# A7_CONNECTOR_V2_0.net
KiCad netlist of a schematic drawn in Altium Designer
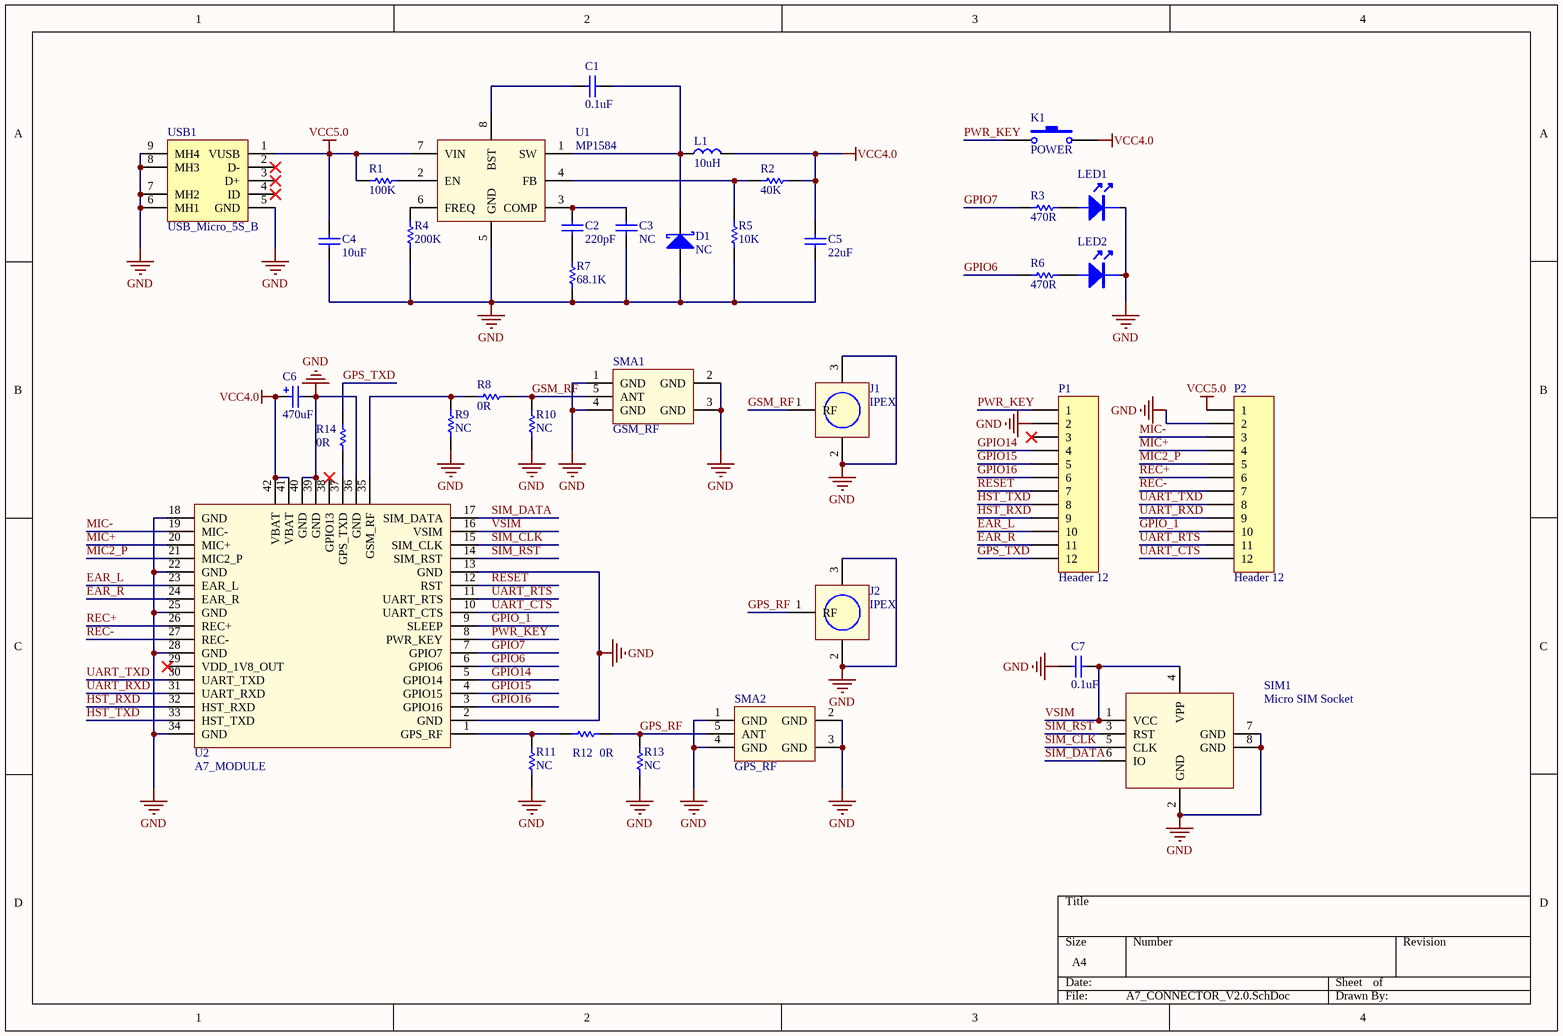
[diagram p0: A7_CONNECTOR_V2.0.SchDoc]

(export (version "E")
  (design (tool "Eeschema 10.0.6"))
  (components
    (comp (ref "C1") (value "0.1uF") (footprint "C0402") (libsource (lib "Schlib1") (part "Cap")))
    (comp (ref "C2") (value "220pF") (footprint "C0402") (libsource (lib "Schlib1") (part "Cap")))
    (comp (ref "C3") (value "NC") (footprint "C0402") (libsource (lib "Schlib1") (part "Cap")))
    (comp (ref "C4") (value "10uF") (footprint "C0603") (libsource (lib "Schlib1") (part "Cap")))
    (comp (ref "C5") (value "22uF") (footprint "C0805") (libsource (lib "Schlib1") (part "Cap")))
    (comp (ref "C6") (value "470uF") (footprint "D7343-31") (libsource (lib "Schlib1") (part "Cap+")))
    (comp (ref "C7") (value "0.1uF") (footprint "C0402") (libsource (lib "Schlib1") (part "Cap")))
    (comp (ref "D1")
      (value "NC")
      (footprint "SOD-123")
      (description "Schottky Diode")
      (fields (field (name "PUBLISHER") "Altium Limited"))
      (libsource (lib "Schlib1") (part "D Schottky"))
    )
    (comp (ref "J1") (value "IPEX") (footprint "IPEX") (libsource (lib "Schlib1") (part "IPEX")))
    (comp (ref "J2") (value "IPEX") (footprint "IPEX") (libsource (lib "Schlib1") (part "IPEX")))
    (comp (ref "K1")
      (value "POWER")
      (footprint "KEY-6*6-SMD")
      (fields (field (name "PUBLISHER") "Altium Limited"))
      (libsource (lib "Schlib1") (part "KEY"))
    )
    (comp (ref "L1") (value "10uH") (footprint "L0805") (libsource (lib "Schlib1") (part "L")))
    (comp (ref "LED1")
      (value "~")
      (footprint "LED_0603")
      (description "SMD0603 LED")
      (libsource (lib "Schlib1") (part "LED"))
    )
    (comp (ref "LED2")
      (value "~")
      (footprint "LED_0603")
      (description "SMD0603 LED")
      (libsource (lib "Schlib1") (part "LED"))
    )
    (comp (ref "P1")
      (value "Header 12")
      (footprint "HDR1X12")
      (description "Header, 12-Pin")
      (fields (field (name "PUBLISHER") "Altium Limited"))
      (libsource (lib "Miscellaneous Connectors") (part "Header 12"))
    )
    (comp (ref "P2")
      (value "Header 12")
      (footprint "HDR1X12")
      (description "Header, 12-Pin")
      (fields (field (name "PUBLISHER") "Altium Limited"))
      (libsource (lib "Miscellaneous Connectors") (part "Header 12"))
    )
    (comp (ref "R1") (value "100K") (footprint "R0402") (libsource (lib "Schlib1") (part "Res")))
    (comp (ref "R2") (value "40K") (footprint "R0402") (libsource (lib "Schlib1") (part "Res")))
    (comp (ref "R3") (value "470R") (footprint "R0402") (libsource (lib "Schlib1") (part "Res")))
    (comp (ref "R4") (value "200K") (footprint "R0402") (libsource (lib "Schlib1") (part "Res")))
    (comp (ref "R5") (value "10K") (footprint "R0402") (libsource (lib "Schlib1") (part "Res")))
    (comp (ref "R6") (value "470R") (footprint "R0402") (libsource (lib "Schlib1") (part "Res")))
    (comp (ref "R7") (value "68.1K") (footprint "R0402") (libsource (lib "Schlib1") (part "Res")))
    (comp (ref "R8") (value "0R") (footprint "R0402") (libsource (lib "Schlib1") (part "Res")))
    (comp (ref "R9") (value "NC") (footprint "R0402") (libsource (lib "Schlib1") (part "Res")))
    (comp (ref "R10") (value "NC") (footprint "R0402") (libsource (lib "Schlib1") (part "Res")))
    (comp (ref "R11") (value "NC") (footprint "R0402") (libsource (lib "Schlib1") (part "Res")))
    (comp (ref "R12") (value "0R") (footprint "R0402") (libsource (lib "Schlib1") (part "Res")))
    (comp (ref "R13") (value "NC") (footprint "R0402") (libsource (lib "Schlib1") (part "Res")))
    (comp (ref "R14") (value "0R") (footprint "R0402") (libsource (lib "Schlib1") (part "Res")))
    (comp (ref "SIM1")
      (value "Micro SIM Socket")
      (footprint "SIM")
      (libsource (lib "Schlib1") (part "Micro SIM"))
    )
    (comp (ref "SMA1") (value "GSM_RF") (footprint "SMA") (libsource (lib "Schlib1") (part "SMA")))
    (comp (ref "SMA2") (value "GPS_RF") (footprint "SMA") (libsource (lib "Schlib1") (part "SMA")))
    (comp (ref "U1") (value "MP1584") (footprint "SOIC8E") (libsource (lib "Schlib1") (part "MP1584")))
    (comp (ref "U2")
      (value "A7_MODULE")
      (footprint "A6_GPS_MODULE")
      (libsource (lib "Schlib1") (part "A6_GPS_MODULE"))
    )
    (comp (ref "USB1")
      (value "USB_Micro_5S_B")
      (footprint "USB_MICRO_5S_B")
      (description "USB micro female SMT with 4 fixed foot")
      (libsource (lib "Schlib1") (part "USB_Micro_5S_B"))
    )
  )
  (nets
    (net (code "1") (name "/EAR_L") (class "Default")
      (node (ref "P1") (pin "10") (pinfunction "10_10") (pintype "passive"))
      (node (ref "U2") (pin "23") (pinfunction "EAR_L_23") (pintype "passive"))
    )
    (net (code "2") (name "/EAR_R") (class "Default")
      (node (ref "P1") (pin "11") (pinfunction "11_11") (pintype "passive"))
      (node (ref "U2") (pin "24") (pinfunction "EAR_R_24") (pintype "passive"))
    )
    (net (code "3") (name "/GPIO6") (class "Default")
      (node (ref "R6") (pin "1") (pinfunction "1_1") (pintype "passive"))
      (node (ref "U2") (pin "6") (pinfunction "GPIO6_6") (pintype "passive"))
    )
    (net (code "4") (name "/GPIO7") (class "Default")
      (node (ref "R3") (pin "1") (pinfunction "1_1") (pintype "passive"))
      (node (ref "U2") (pin "7") (pinfunction "GPIO7_7") (pintype "passive"))
    )
    (net (code "5") (name "/GPIO14") (class "Default")
      (node (ref "P1") (pin "4") (pinfunction "4_4") (pintype "passive"))
      (node (ref "U2") (pin "5") (pinfunction "GPIO14_5") (pintype "passive"))
    )
    (net (code "6") (name "/GPIO15") (class "Default")
      (node (ref "P1") (pin "5") (pinfunction "5_5") (pintype "passive"))
      (node (ref "U2") (pin "4") (pinfunction "GPIO15_4") (pintype "passive"))
    )
    (net (code "7") (name "/GPIO16") (class "Default")
      (node (ref "P1") (pin "6") (pinfunction "6_6") (pintype "passive"))
      (node (ref "U2") (pin "3") (pinfunction "GPIO16_3") (pintype "passive"))
    )
    (net (code "8") (name "/GPIO_1") (class "Default")
      (node (ref "P2") (pin "10") (pinfunction "10_10") (pintype "passive"))
      (node (ref "U2") (pin "9") (pinfunction "SLEEP_9") (pintype "passive"))
    )
    (net (code "9") (name "/GPS_RF") (class "Default")
      (node (ref "J2") (pin "1") (pinfunction "RF_1") (pintype "passive"))
      (node (ref "R12") (pin "2") (pinfunction "2_2") (pintype "passive"))
      (node (ref "R13") (pin "2") (pinfunction "2_2") (pintype "passive"))
      (node (ref "SMA2") (pin "5") (pinfunction "ANT_5") (pintype "passive"))
    )
    (net (code "10") (name "/GPS_TXD") (class "Default")
      (node (ref "P1") (pin "12") (pinfunction "12_12") (pintype "passive"))
      (node (ref "R14") (pin "2") (pinfunction "2_2") (pintype "passive"))
    )
    (net (code "11") (name "/GSM_RF") (class "Default")
      (node (ref "J1") (pin "1") (pinfunction "RF_1") (pintype "passive"))
      (node (ref "R10") (pin "2") (pinfunction "2_2") (pintype "passive"))
      (node (ref "R8") (pin "2") (pinfunction "2_2") (pintype "passive"))
      (node (ref "SMA1") (pin "5") (pinfunction "ANT_5") (pintype "passive"))
    )
    (net (code "12") (name "/HST_RXD") (class "Default")
      (node (ref "P1") (pin "9") (pinfunction "9_9") (pintype "passive"))
      (node (ref "U2") (pin "32") (pinfunction "HST_RXD_32") (pintype "passive"))
    )
    (net (code "13") (name "/HST_TXD") (class "Default")
      (node (ref "P1") (pin "8") (pinfunction "8_8") (pintype "passive"))
      (node (ref "U2") (pin "33") (pinfunction "HST_TXD_33") (pintype "passive"))
    )
    (net (code "14") (name "/MIC+") (class "Default")
      (node (ref "P2") (pin "4") (pinfunction "4_4") (pintype "passive"))
      (node (ref "U2") (pin "20") (pinfunction "MIC+_20") (pintype "passive"))
    )
    (net (code "15") (name "/MIC-") (class "Default")
      (node (ref "P2") (pin "3") (pinfunction "3_3") (pintype "passive"))
      (node (ref "U2") (pin "19") (pinfunction "MIC-_19") (pintype "passive"))
    )
    (net (code "16") (name "/MIC2_P") (class "Default")
      (node (ref "P2") (pin "5") (pinfunction "5_5") (pintype "passive"))
      (node (ref "U2") (pin "21") (pinfunction "MIC2_P_21") (pintype "passive"))
    )
    (net (code "17") (name "/PWR_KEY") (class "Default")
      (node (ref "K1") (pin "1") (pinfunction "1_1") (pintype "passive"))
      (node (ref "P1") (pin "1") (pinfunction "1_1") (pintype "passive"))
      (node (ref "U2") (pin "8") (pinfunction "PWR_KEY_8") (pintype "passive"))
    )
    (net (code "18") (name "/REC+") (class "Default")
      (node (ref "P2") (pin "6") (pinfunction "6_6") (pintype "passive"))
      (node (ref "U2") (pin "26") (pinfunction "REC+_26") (pintype "passive"))
    )
    (net (code "19") (name "/REC-") (class "Default")
      (node (ref "P2") (pin "7") (pinfunction "7_7") (pintype "passive"))
      (node (ref "U2") (pin "27") (pinfunction "REC-_27") (pintype "passive"))
    )
    (net (code "20") (name "/RESET") (class "Default")
      (node (ref "P1") (pin "7") (pinfunction "7_7") (pintype "passive"))
      (node (ref "U2") (pin "12") (pinfunction "RST_12") (pintype "passive"))
    )
    (net (code "21") (name "/SIM_CLK") (class "Default")
      (node (ref "SIM1") (pin "5") (pinfunction "CLK_5") (pintype "passive"))
      (node (ref "U2") (pin "15") (pinfunction "SIM_CLK_15") (pintype "passive"))
    )
    (net (code "22") (name "/SIM_DATA") (class "Default")
      (node (ref "SIM1") (pin "6") (pinfunction "IO_6") (pintype "passive"))
      (node (ref "U2") (pin "17") (pinfunction "SIM_DATA_17") (pintype "passive"))
    )
    (net (code "23") (name "/SIM_RST") (class "Default")
      (node (ref "SIM1") (pin "3") (pinfunction "RST_3") (pintype "passive"))
      (node (ref "U2") (pin "14") (pinfunction "SIM_RST_14") (pintype "passive"))
    )
    (net (code "24") (name "/UART_CTS") (class "Default")
      (node (ref "P2") (pin "12") (pinfunction "12_12") (pintype "passive"))
      (node (ref "U2") (pin "10") (pinfunction "UART_CTS_10") (pintype "passive"))
    )
    (net (code "25") (name "/UART_RTS") (class "Default")
      (node (ref "P2") (pin "11") (pinfunction "11_11") (pintype "passive"))
      (node (ref "U2") (pin "11") (pinfunction "UART_RTS_11") (pintype "passive"))
    )
    (net (code "26") (name "/UART_RXD") (class "Default")
      (node (ref "P2") (pin "9") (pinfunction "9_9") (pintype "passive"))
      (node (ref "U2") (pin "31") (pinfunction "UART_RXD_31") (pintype "passive"))
    )
    (net (code "27") (name "/UART_TXD") (class "Default")
      (node (ref "P2") (pin "8") (pinfunction "8_8") (pintype "passive"))
      (node (ref "U2") (pin "30") (pinfunction "UART_TXD_30") (pintype "passive"))
    )
    (net (code "28") (name "/VSIM") (class "Default")
      (node (ref "C7") (pin "1") (pinfunction "1_1") (pintype "passive"))
      (node (ref "SIM1") (pin "1") (pinfunction "VCC_1") (pintype "passive"))
      (node (ref "SIM1") (pin "4") (pinfunction "VPP_4") (pintype "passive"))
      (node (ref "U2") (pin "16") (pinfunction "VSIM_16") (pintype "passive"))
    )
    (net (code "29") (name "GND") (class "Default")
      (node (ref "C3") (pin "1") (pinfunction "1_1") (pintype "passive"))
      (node (ref "C4") (pin "1") (pinfunction "1_1") (pintype "passive"))
      (node (ref "C5") (pin "1") (pinfunction "1_1") (pintype "passive"))
      (node (ref "C6") (pin "2") (pinfunction "2_2") (pintype "passive"))
      (node (ref "C7") (pin "2") (pinfunction "2_2") (pintype "passive"))
      (node (ref "D1") (pin "1") (pinfunction "A_1") (pintype "passive"))
      (node (ref "J1") (pin "2") (pinfunction "GND_2") (pintype "passive"))
      (node (ref "J1") (pin "3") (pinfunction "GND_3") (pintype "passive"))
      (node (ref "J2") (pin "2") (pinfunction "GND_2") (pintype "passive"))
      (node (ref "J2") (pin "3") (pinfunction "GND_3") (pintype "passive"))
      (node (ref "LED1") (pin "2") (pinfunction "K_2") (pintype "passive"))
      (node (ref "LED2") (pin "2") (pinfunction "K_2") (pintype "passive"))
      (node (ref "P1") (pin "2") (pinfunction "2_2") (pintype "passive"))
      (node (ref "P2") (pin "2") (pinfunction "2_2") (pintype "passive"))
      (node (ref "R10") (pin "1") (pinfunction "1_1") (pintype "passive"))
      (node (ref "R11") (pin "1") (pinfunction "1_1") (pintype "passive"))
      (node (ref "R13") (pin "1") (pinfunction "1_1") (pintype "passive"))
      (node (ref "R4") (pin "1") (pinfunction "1_1") (pintype "passive"))
      (node (ref "R5") (pin "1") (pinfunction "1_1") (pintype "passive"))
      (node (ref "R7") (pin "1") (pinfunction "1_1") (pintype "passive"))
      (node (ref "R9") (pin "1") (pinfunction "1_1") (pintype "passive"))
      (node (ref "SIM1") (pin "2") (pinfunction "GND_2") (pintype "passive"))
      (node (ref "SIM1") (pin "7") (pinfunction "GND_7") (pintype "passive"))
      (node (ref "SIM1") (pin "8") (pinfunction "GND_8") (pintype "passive"))
      (node (ref "SMA1") (pin "1") (pinfunction "GND_1") (pintype "passive"))
      (node (ref "SMA1") (pin "2") (pinfunction "GND_2") (pintype "passive"))
      (node (ref "SMA1") (pin "3") (pinfunction "GND_3") (pintype "passive"))
      (node (ref "SMA1") (pin "4") (pinfunction "GND_4") (pintype "passive"))
      (node (ref "SMA2") (pin "1") (pinfunction "GND_1") (pintype "passive"))
      (node (ref "SMA2") (pin "2") (pinfunction "GND_2") (pintype "passive"))
      (node (ref "SMA2") (pin "3") (pinfunction "GND_3") (pintype "passive"))
      (node (ref "SMA2") (pin "4") (pinfunction "GND_4") (pintype "passive"))
      (node (ref "U1") (pin "5") (pinfunction "GND_5") (pintype "passive"))
      (node (ref "U2") (pin "13") (pinfunction "GND_13") (pintype "passive"))
      (node (ref "U2") (pin "18") (pinfunction "GND_18") (pintype "passive"))
      (node (ref "U2") (pin "2") (pinfunction "GND_2") (pintype "passive"))
      (node (ref "U2") (pin "22") (pinfunction "GND_22") (pintype "passive"))
      (node (ref "U2") (pin "25") (pinfunction "GND_25") (pintype "passive"))
      (node (ref "U2") (pin "28") (pinfunction "GND_28") (pintype "passive"))
      (node (ref "U2") (pin "34") (pinfunction "GND_34") (pintype "passive"))
      (node (ref "U2") (pin "36") (pinfunction "GND_36") (pintype "passive"))
      (node (ref "U2") (pin "39") (pinfunction "GND_39") (pintype "passive"))
      (node (ref "U2") (pin "40") (pinfunction "GND_40") (pintype "passive"))
      (node (ref "USB1") (pin "5") (pinfunction "GND_5") (pintype "passive"))
      (node (ref "USB1") (pin "6") (pinfunction "MH1_6") (pintype "passive"))
      (node (ref "USB1") (pin "7") (pinfunction "MH2_7") (pintype "passive"))
      (node (ref "USB1") (pin "8") (pinfunction "MH3_8") (pintype "passive"))
      (node (ref "USB1") (pin "9") (pinfunction "MH4_9") (pintype "passive"))
    )
    (net (code "30") (name "Net-(C2-Pad1)") (class "Default")
      (node (ref "C2") (pin "1") (pinfunction "1_1") (pintype "passive"))
      (node (ref "R7") (pin "2") (pinfunction "2_2") (pintype "passive"))
    )
    (net (code "31") (name "Net-(D1-K)") (class "Default")
      (node (ref "C1") (pin "2") (pinfunction "2_2") (pintype "passive"))
      (node (ref "D1") (pin "2") (pinfunction "K_2") (pintype "passive"))
      (node (ref "L1") (pin "2") (pinfunction "2_2") (pintype "passive"))
      (node (ref "U1") (pin "1") (pinfunction "SW_1") (pintype "passive"))
    )
    (net (code "32") (name "Net-(LED1-A)") (class "Default")
      (node (ref "LED1") (pin "1") (pinfunction "A_1") (pintype "passive"))
      (node (ref "R3") (pin "2") (pinfunction "2_2") (pintype "passive"))
    )
    (net (code "33") (name "Net-(LED2-A)") (class "Default")
      (node (ref "LED2") (pin "1") (pinfunction "A_1") (pintype "passive"))
      (node (ref "R6") (pin "2") (pinfunction "2_2") (pintype "passive"))
    )
    (net (code "34") (name "Net-(U1-BST)") (class "Default")
      (node (ref "C1") (pin "1") (pinfunction "1_1") (pintype "passive"))
      (node (ref "U1") (pin "8") (pinfunction "BST_8") (pintype "passive"))
    )
    (net (code "35") (name "Net-(U1-COMP)") (class "Default")
      (node (ref "C2") (pin "2") (pinfunction "2_2") (pintype "passive"))
      (node (ref "C3") (pin "2") (pinfunction "2_2") (pintype "passive"))
      (node (ref "U1") (pin "3") (pinfunction "COMP_3") (pintype "passive"))
    )
    (net (code "36") (name "Net-(U1-EN)") (class "Default")
      (node (ref "R1") (pin "2") (pinfunction "2_2") (pintype "passive"))
      (node (ref "U1") (pin "2") (pinfunction "EN_2") (pintype "passive"))
    )
    (net (code "37") (name "Net-(U1-FB)") (class "Default")
      (node (ref "R2") (pin "2") (pinfunction "2_2") (pintype "passive"))
      (node (ref "R5") (pin "2") (pinfunction "2_2") (pintype "passive"))
      (node (ref "U1") (pin "4") (pinfunction "FB_4") (pintype "passive"))
    )
    (net (code "38") (name "Net-(U1-FREQ)") (class "Default")
      (node (ref "R4") (pin "2") (pinfunction "2_2") (pintype "passive"))
      (node (ref "U1") (pin "6") (pinfunction "FREQ_6") (pintype "passive"))
    )
    (net (code "39") (name "Net-(U2-GPS_RF)") (class "Default")
      (node (ref "R11") (pin "2") (pinfunction "2_2") (pintype "passive"))
      (node (ref "R12") (pin "1") (pinfunction "1_1") (pintype "passive"))
      (node (ref "U2") (pin "1") (pinfunction "GPS_RF_1") (pintype "passive"))
    )
    (net (code "40") (name "Net-(U2-GPS_TXD)") (class "Default")
      (node (ref "R14") (pin "1") (pinfunction "1_1") (pintype "passive"))
      (node (ref "U2") (pin "37") (pinfunction "GPS_TXD_37") (pintype "passive"))
    )
    (net (code "41") (name "Net-(U2-GSM_RF)") (class "Default")
      (node (ref "R8") (pin "1") (pinfunction "1_1") (pintype "passive"))
      (node (ref "R9") (pin "2") (pinfunction "2_2") (pintype "passive"))
      (node (ref "U2") (pin "35") (pinfunction "GSM_RF_35") (pintype "passive"))
    )
    (net (code "42") (name "VCC4.0") (class "Default")
      (node (ref "C5") (pin "2") (pinfunction "2_2") (pintype "passive"))
      (node (ref "C6") (pin "1") (pinfunction "1_1") (pintype "passive"))
      (node (ref "K1") (pin "2") (pinfunction "2_2") (pintype "passive"))
      (node (ref "L1") (pin "1") (pinfunction "1_1") (pintype "passive"))
      (node (ref "R2") (pin "1") (pinfunction "1_1") (pintype "passive"))
      (node (ref "U2") (pin "41") (pinfunction "VBAT_41") (pintype "passive"))
      (node (ref "U2") (pin "42") (pinfunction "VBAT_42") (pintype "passive"))
    )
    (net (code "43") (name "VCC5.0") (class "Default")
      (node (ref "C4") (pin "2") (pinfunction "2_2") (pintype "passive"))
      (node (ref "P2") (pin "1") (pinfunction "1_1") (pintype "passive"))
      (node (ref "R1") (pin "1") (pinfunction "1_1") (pintype "passive"))
      (node (ref "U1") (pin "7") (pinfunction "VIN_7") (pintype "passive"))
      (node (ref "USB1") (pin "1") (pinfunction "VUSB_1") (pintype "passive"))
    )
    (net (code "44") (name "unconnected-(P1-Pad3)") (class "Default")
      (node (ref "P1") (pin "3") (pinfunction "3_3") (pintype "passive+no_connect"))
    )
    (net (code "45") (name "unconnected-(U2-GPIO13-Pad38)") (class "Default")
      (node (ref "U2") (pin "38") (pinfunction "GPIO13_38") (pintype "passive+no_connect"))
    )
    (net (code "46") (name "unconnected-(U2-VDD_1V8_OUT-Pad29)") (class "Default")
      (node (ref "U2") (pin "29") (pinfunction "VDD_1V8_OUT_29") (pintype "passive+no_connect"))
    )
    (net (code "47") (name "unconnected-(USB1-D+-Pad3)") (class "Default")
      (node (ref "USB1") (pin "3") (pinfunction "D+_3") (pintype "passive+no_connect"))
    )
    (net (code "48") (name "unconnected-(USB1-D--Pad2)") (class "Default")
      (node (ref "USB1") (pin "2") (pinfunction "D-_2") (pintype "passive+no_connect"))
    )
    (net (code "49") (name "unconnected-(USB1-ID-Pad4)") (class "Default")
      (node (ref "USB1") (pin "4") (pinfunction "ID_4") (pintype "passive+no_connect"))
    )
  )
)
